# CAN.net
KiCad netlist of a schematic drawn in Altium Designer
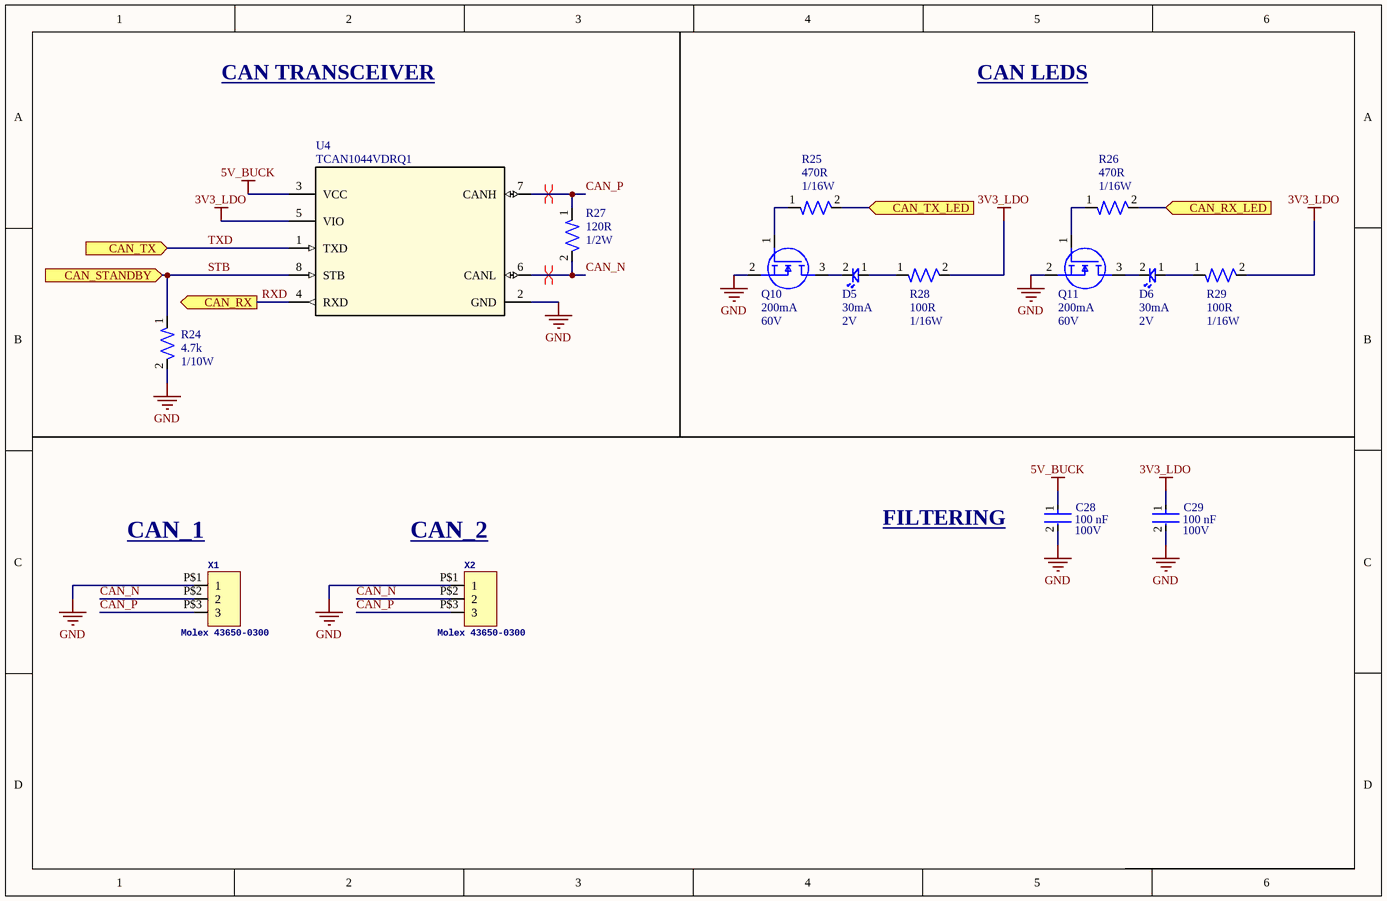
[diagram p0: CAN.SchDoc]

(export (version "E")
  (design (tool "Eeschema 10.0.6"))
  (components
    (comp (ref "C28")
      (value "GRM188R72A104KA35D")
      (footprint "CAP-0603")
      (description "CAP CER 100NF 100V X7R 0603")
      (fields (field (name "CAPACITANCE") "100 nF") (field (name "VOLTAGE") "100V"))
      (libsource (lib "JLC_25") (part "CAP-1U-0002"))
    )
    (comp (ref "C29")
      (value "GRM188R72A104KA35D")
      (footprint "CAP-0603")
      (description "CAP CER 100NF 100V X7R 0603")
      (fields (field (name "CAPACITANCE") "100 nF") (field (name "VOLTAGE") "100V"))
      (libsource (lib "JLC_25") (part "CAP-1U-0002"))
    )
    (comp (ref "D5")
      (value "BL-HKC36G-AV-TRB")
      (footprint "LED-0603")
      (description "LED YELLOW CLEAR 0603 SMD")
      (fields (field (name "FORWARD CURRENT") "30mA") (field (name "FORWARD VOLTAGE") "2V"))
      (libsource (lib "JLC_25") (part "LED-0001"))
    )
    (comp (ref "D6")
      (value "BL-HKC36G-AV-TRB")
      (footprint "LED-0603")
      (description "LED YELLOW CLEAR 0603 SMD")
      (fields (field (name "FORWARD CURRENT") "30mA") (field (name "FORWARD VOLTAGE") "2V"))
      (libsource (lib "JLC_25") (part "LED-0001"))
    )
    (comp (ref "Q10")
      (value "T2N7002AK,LM")
      (footprint "IC-SOT23-3")
      (description "MOSFET N-CH 60V 200MA SOT23")
      (fields (field (name "CONTINUOUS CURRENT") "200mA") (field (name "VOLTAGE") "60V"))
      (libsource (lib "JLC_25") (part "NMOS-200MA-0001"))
    )
    (comp (ref "Q11")
      (value "T2N7002AK,LM")
      (footprint "IC-SOT23-3")
      (description "MOSFET N-CH 60V 200MA SOT23")
      (fields (field (name "CONTINUOUS CURRENT") "200mA") (field (name "VOLTAGE") "60V"))
      (libsource (lib "JLC_25") (part "NMOS-200MA-0001"))
    )
    (comp (ref "R24")
      (value "RC0603FR-074K7L")
      (footprint "RES-0603")
      (description "RES 4.7K OHM 1% 1/10W 0603")
      (fields
        (field (name "TOLERANCE") "1%")
        (field (name "POWER") "1/10W")
        (field (name "RESISTANCE") "4.7k")
      )
      (libsource (lib "JLC_25") (part "RES-4.7k-0001"))
    )
    (comp (ref "R25")
      (value "RC0402FR-07470RL")
      (footprint "RES-0402")
      (description "RES 470 OHM 1% 1/16W 0402")
      (fields
        (field (name "TOLERANCE") "1%")
        (field (name "POWER") "1/16W")
        (field (name "RESISTANCE") "470R")
      )
      (libsource (lib "JLC_25") (part "RES-470-0001"))
    )
    (comp (ref "R26")
      (value "RC0402FR-07470RL")
      (footprint "RES-0402")
      (description "RES 470 OHM 1% 1/16W 0402")
      (fields
        (field (name "TOLERANCE") "1%")
        (field (name "POWER") "1/16W")
        (field (name "RESISTANCE") "470R")
      )
      (libsource (lib "JLC_25") (part "RES-470-0001"))
    )
    (comp (ref "R27")
      (value "RC1210FR-07120RL")
      (footprint "RES-1210")
      (description "RES 120 OHM 1% 1/2W 1210")
      (fields
        (field (name "TOLERANCE") "1%")
        (field (name "POWER") "1/2W")
        (field (name "RESISTANCE") "120R")
      )
      (libsource (lib "JLC_25") (part "RES-120-0001"))
    )
    (comp (ref "R28")
      (value "RC0402FR-07100RL")
      (footprint "RES-0402")
      (description "RES 100 OHM 1% 1/16W 0402")
      (fields
        (field (name "TOLERANCE") "1%")
        (field (name "POWER") "1/16W")
        (field (name "RESISTANCE") "100R")
      )
      (libsource (lib "JLC_25") (part "RES-100-0001"))
    )
    (comp (ref "R29")
      (value "RC0402FR-07100RL")
      (footprint "RES-0402")
      (description "RES 100 OHM 1% 1/16W 0402")
      (fields
        (field (name "TOLERANCE") "1%")
        (field (name "POWER") "1/16W")
        (field (name "RESISTANCE") "100R")
      )
      (libsource (lib "JLC_25") (part "RES-100-0001"))
    )
    (comp (ref "U4")
      (value "TCAN1044VDRQ1")
      (footprint "IC-8SOIC")
      (description "IC TRANSCEIVER 1/1 8SOIC")
      (libsource (lib "JLC_25") (part "IC-CAN-0001"))
    )
    (comp (ref "X1")
      (value "Molex 43650-0300")
      (footprint "43650-0300")
      (libsource (lib "Molex Microfit") (part "Micro-Fit Molex 3 Pin Right Angle"))
    )
    (comp (ref "X2")
      (value "Molex 43650-0300")
      (footprint "43650-0300")
      (libsource (lib "Molex Microfit") (part "Micro-Fit Molex 3 Pin Right Angle"))
    )
  )
  (nets
    (net (code "1") (name "/CAN_N") (class "Default")
      (node (ref "R27") (pin "2") (pinfunction "2_2") (pintype "passive"))
      (node (ref "U4") (pin "6") (pinfunction "CANL_6") (pintype "bidirectional"))
      (node (ref "X1") (pin "P$2") (pinfunction "2_P$2") (pintype "passive"))
      (node (ref "X2") (pin "P$2") (pinfunction "2_P$2") (pintype "passive"))
    )
    (net (code "2") (name "/CAN_P") (class "Default")
      (node (ref "R27") (pin "1") (pinfunction "1_1") (pintype "passive"))
      (node (ref "U4") (pin "7") (pinfunction "CANH_7") (pintype "bidirectional"))
      (node (ref "X1") (pin "P$3") (pinfunction "3_P$3") (pintype "passive"))
      (node (ref "X2") (pin "P$3") (pinfunction "3_P$3") (pintype "passive"))
    )
    (net (code "3") (name "/CAN_RX_LED") (class "Default")
      (node (ref "R26") (pin "2") (pinfunction "2_2") (pintype "passive"))
    )
    (net (code "4") (name "/CAN_TX_LED") (class "Default")
      (node (ref "R25") (pin "2") (pinfunction "2_2") (pintype "passive"))
    )
    (net (code "5") (name "/RXD") (class "Default")
      (node (ref "U4") (pin "4") (pinfunction "RXD_4") (pintype "output"))
    )
    (net (code "6") (name "/STB") (class "Default")
      (node (ref "R24") (pin "1") (pinfunction "1_1") (pintype "passive"))
      (node (ref "U4") (pin "8") (pinfunction "STB_8") (pintype "input"))
    )
    (net (code "7") (name "/TXD") (class "Default")
      (node (ref "U4") (pin "1") (pinfunction "TXD_1") (pintype "input"))
    )
    (net (code "8") (name "3V3_LDO") (class "Default")
      (node (ref "C29") (pin "1") (pinfunction "1_1") (pintype "passive"))
      (node (ref "R28") (pin "2") (pinfunction "2_2") (pintype "passive"))
      (node (ref "R29") (pin "2") (pinfunction "2_2") (pintype "passive"))
      (node (ref "U4") (pin "5") (pinfunction "VIO_5") (pintype "power_in"))
    )
    (net (code "9") (name "5V_BUCK") (class "Default")
      (node (ref "C28") (pin "1") (pinfunction "1_1") (pintype "passive"))
      (node (ref "U4") (pin "3") (pinfunction "VCC_3") (pintype "power_in"))
    )
    (net (code "10") (name "GND") (class "Default")
      (node (ref "C28") (pin "2") (pinfunction "2_2") (pintype "passive"))
      (node (ref "C29") (pin "2") (pinfunction "2_2") (pintype "passive"))
      (node (ref "Q10") (pin "2") (pinfunction "S_2") (pintype "passive"))
      (node (ref "Q11") (pin "2") (pinfunction "S_2") (pintype "passive"))
      (node (ref "R24") (pin "2") (pinfunction "2_2") (pintype "passive"))
      (node (ref "U4") (pin "2") (pinfunction "GND_2") (pintype "power_in"))
      (node (ref "X1") (pin "P$1") (pinfunction "1_P$1") (pintype "passive"))
      (node (ref "X2") (pin "P$1") (pinfunction "1_P$1") (pintype "passive"))
    )
    (net (code "11") (name "Net-(D5-Pad1)") (class "Default")
      (node (ref "D5") (pin "1") (pinfunction "1_1") (pintype "passive"))
      (node (ref "R28") (pin "1") (pinfunction "1_1") (pintype "passive"))
    )
    (net (code "12") (name "Net-(D6-Pad1)") (class "Default")
      (node (ref "D6") (pin "1") (pinfunction "1_1") (pintype "passive"))
      (node (ref "R29") (pin "1") (pinfunction "1_1") (pintype "passive"))
    )
    (net (code "13") (name "Net-(Q10-D)") (class "Default")
      (node (ref "D5") (pin "2") (pinfunction "2_2") (pintype "passive"))
      (node (ref "Q10") (pin "3") (pinfunction "D_3") (pintype "passive"))
    )
    (net (code "14") (name "Net-(Q10-G)") (class "Default")
      (node (ref "Q10") (pin "1") (pinfunction "G_1") (pintype "passive"))
      (node (ref "R25") (pin "1") (pinfunction "1_1") (pintype "passive"))
    )
    (net (code "15") (name "Net-(Q11-D)") (class "Default")
      (node (ref "D6") (pin "2") (pinfunction "2_2") (pintype "passive"))
      (node (ref "Q11") (pin "3") (pinfunction "D_3") (pintype "passive"))
    )
    (net (code "16") (name "Net-(Q11-G)") (class "Default")
      (node (ref "Q11") (pin "1") (pinfunction "G_1") (pintype "passive"))
      (node (ref "R26") (pin "1") (pinfunction "1_1") (pintype "passive"))
    )
  )
)
